# xmos.net
KiCad netlist of a schematic drawn in Altium Designer
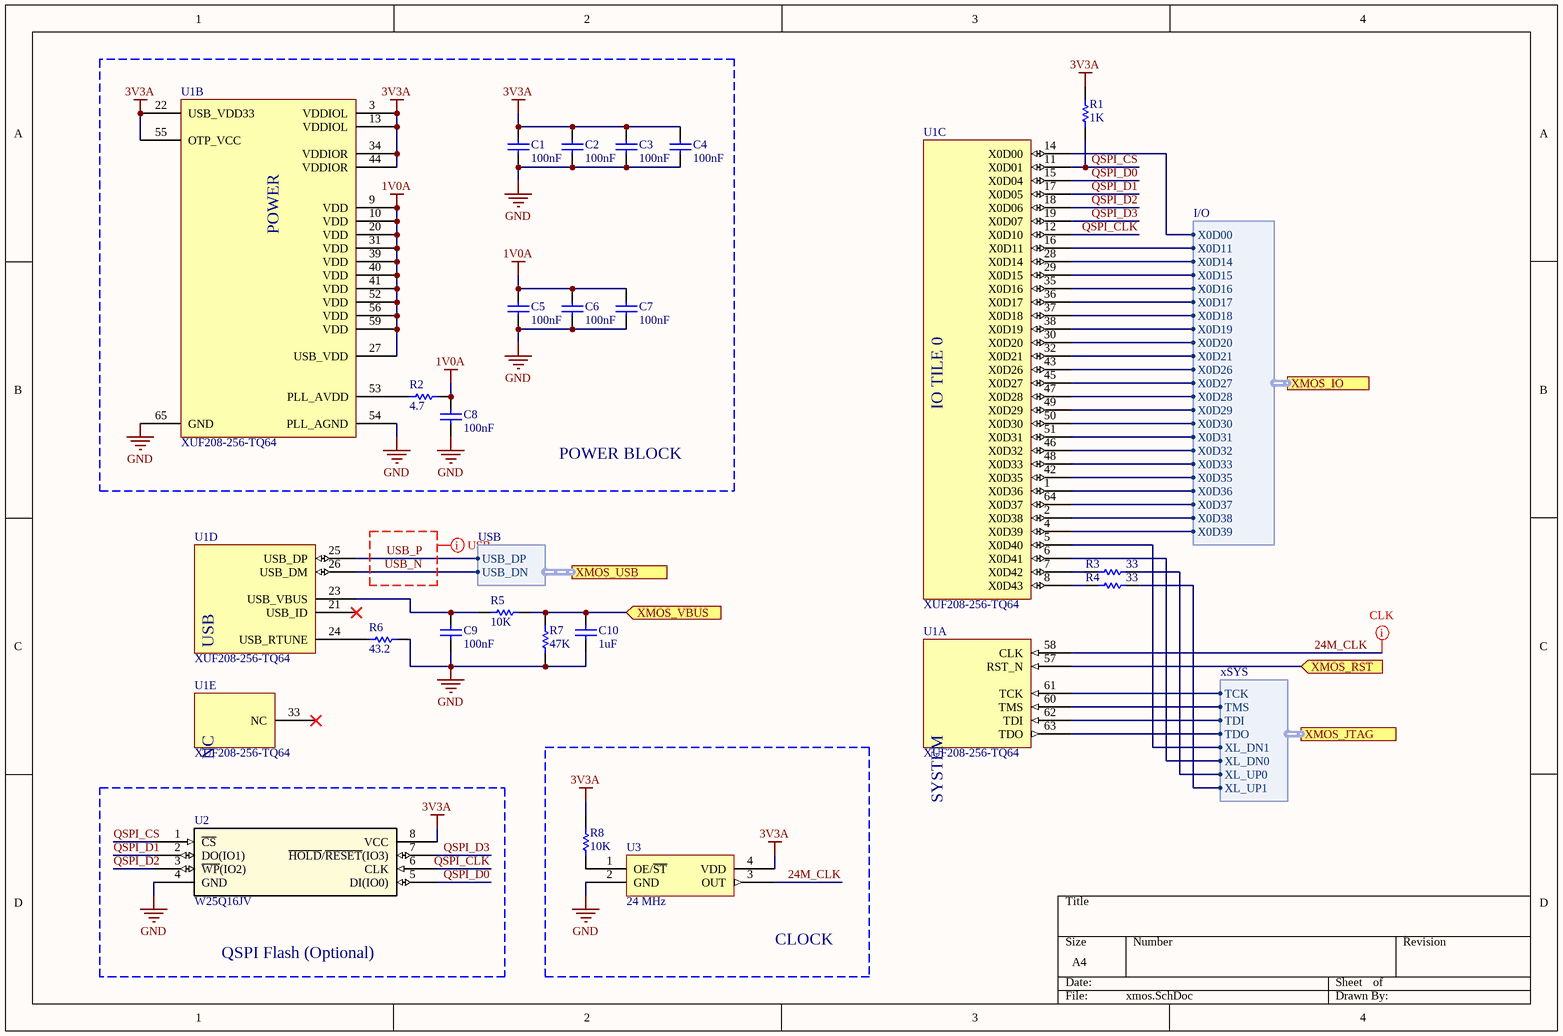
[diagram p0: xmos.SchDoc]

(export (version "E")
  (design (tool "Eeschema 10.0.6"))
  (components
    (comp (ref "C1")
      (value "100nF")
      (footprint "CAP_0603")
      (description "Multilayer Ceramic Capacitors")
      (fields (field (name "TOLERANCE") "10%") (field (name "Comment") "MLCC"))
      (libsource (lib "Capacitors") (part "MLCC"))
    )
    (comp (ref "C2")
      (value "100nF")
      (footprint "CAP_0603")
      (description "Multilayer Ceramic Capacitors")
      (fields (field (name "TOLERANCE") "10%") (field (name "Comment") "MLCC"))
      (libsource (lib "Capacitors") (part "MLCC"))
    )
    (comp (ref "C3")
      (value "100nF")
      (footprint "CAP_0603")
      (description "Multilayer Ceramic Capacitors")
      (fields (field (name "TOLERANCE") "10%") (field (name "Comment") "MLCC"))
      (libsource (lib "Capacitors") (part "MLCC"))
    )
    (comp (ref "C4")
      (value "100nF")
      (footprint "CAP_0603")
      (description "Multilayer Ceramic Capacitors")
      (fields (field (name "TOLERANCE") "10%") (field (name "Comment") "MLCC"))
      (libsource (lib "Capacitors") (part "MLCC"))
    )
    (comp (ref "C5")
      (value "100nF")
      (footprint "CAP_0603")
      (description "Multilayer Ceramic Capacitors")
      (fields (field (name "TOLERANCE") "10%") (field (name "Comment") "MLCC"))
      (libsource (lib "Capacitors") (part "MLCC"))
    )
    (comp (ref "C6")
      (value "100nF")
      (footprint "CAP_0603")
      (description "Multilayer Ceramic Capacitors")
      (fields (field (name "TOLERANCE") "10%") (field (name "Comment") "MLCC"))
      (libsource (lib "Capacitors") (part "MLCC"))
    )
    (comp (ref "C7")
      (value "100nF")
      (footprint "CAP_0603")
      (description "Multilayer Ceramic Capacitors")
      (fields (field (name "TOLERANCE") "10%") (field (name "Comment") "MLCC"))
      (libsource (lib "Capacitors") (part "MLCC"))
    )
    (comp (ref "C8")
      (value "100nF")
      (footprint "CAP_0603")
      (description "Multilayer Ceramic Capacitors")
      (fields (field (name "TOLERANCE") "10%") (field (name "Comment") "MLCC"))
      (libsource (lib "Capacitors") (part "MLCC"))
    )
    (comp (ref "C9")
      (value "100nF")
      (footprint "CAP_0603")
      (description "Multilayer Ceramic Capacitors")
      (fields (field (name "TOLERANCE") "10%") (field (name "Comment") "MLCC"))
      (libsource (lib "Capacitors") (part "MLCC"))
    )
    (comp (ref "C10")
      (value "1uF")
      (footprint "CAP_0603")
      (description "Multilayer Ceramic Capacitors")
      (fields (field (name "TOLERANCE") "10%") (field (name "Comment") "MLCC"))
      (libsource (lib "Capacitors") (part "MLCC"))
    )
    (comp (ref "R1")
      (value "1K")
      (footprint "RC0603N")
      (description "Chip Resistors")
      (fields (field (name "Comment") "RES"))
      (libsource (lib "Resistors") (part "RES"))
    )
    (comp (ref "R2")
      (value "4.7")
      (footprint "RC0603N")
      (description "Chip Resistors")
      (fields (field (name "Comment") "RES"))
      (libsource (lib "Resistors") (part "RES"))
    )
    (comp (ref "R3")
      (value "33")
      (footprint "RC0603N")
      (description "Chip Resistors")
      (fields (field (name "Comment") "RES"))
      (libsource (lib "Resistors") (part "RES"))
    )
    (comp (ref "R4")
      (value "33")
      (footprint "RC0603N")
      (description "Chip Resistors")
      (fields (field (name "Comment") "RES"))
      (libsource (lib "Resistors") (part "RES"))
    )
    (comp (ref "R5")
      (value "10K")
      (footprint "RC0603N")
      (description "Chip Resistors")
      (fields (field (name "Comment") "RES"))
      (libsource (lib "Resistors") (part "RES"))
    )
    (comp (ref "R6")
      (value "43.2")
      (footprint "RC0603N")
      (description "Chip Resistors")
      (fields (field (name "Comment") "RES"))
      (libsource (lib "Resistors") (part "RES"))
    )
    (comp (ref "R7")
      (value "47K")
      (footprint "RC0603N")
      (description "Chip Resistors")
      (fields (field (name "Comment") "RES"))
      (libsource (lib "Resistors") (part "RES"))
    )
    (comp (ref "R8")
      (value "10K")
      (footprint "RC0603N")
      (description "Chip Resistors")
      (fields (field (name "Comment") "RES"))
      (libsource (lib "Resistors") (part "RES"))
    )
    (comp (ref "U1")
      (value "XUF208-256-TQ64")
      (footprint "TQ64")
      (description "xCORE Multicore Microcontroller, xCORE-200, USB, Single Tile, 8 Cores, 500MHz, 64TQFP")
      (fields (field (name "MANUFACTURER") "XMOS"))
      (libsource (lib "XMOS") (part "XUF208-256-TQ64"))
    )
    (comp (ref "U2")
      (value "W25Q16JV")
      (footprint "SOIC-8_150MIL")
      (description "3V 16M-BIT SERIAL FLASH MEMORY WITH DUAL/QUAD SPI")
      (fields
        (field (name "MANUFACTURER_PART_NUMBER") "W25Q16JVXXXX")
        (field (name "COPYRIGHT") "Copyright (C) 2018 Accelerated Designs. All rights reserved")
      )
      (libsource (lib "WINBOND") (part "W25Q16JV"))
    )
    (comp (ref "U3")
      (value "XO")
      (footprint "QFN_3225_4P")
      (description "SiTime Ultra Performance Oscillator")
      (fields (field (name "MANUFACTURER") "SiTime") (field (name "FREQUENCY") "24 MHz"))
      (libsource (lib "Crystals") (part "XO"))
    )
  )
  (nets
    (net (code "4") (name "/24M_CLK") (class "Default")
      (node (ref "U1") (pin "58") (pinfunction "CLK_58") (pintype "input"))
      (node (ref "U3") (pin "3") (pinfunction "OUT_3") (pintype "output"))
    )
    (net (code "5") (name "/QSPI_CLK") (class "Default")
      (node (ref "U1") (pin "12") (pinfunction "X0D10_12") (pintype "bidirectional"))
      (node (ref "U2") (pin "6") (pinfunction "CLK_6") (pintype "input"))
    )
    (net (code "6") (name "/QSPI_CS") (class "Default")
      (node (ref "R1") (pin "1") (pinfunction "1_1") (pintype "passive"))
      (node (ref "U1") (pin "11") (pinfunction "X0D01_11") (pintype "bidirectional"))
      (node (ref "U2") (pin "1") (pinfunction "~{CS}_1") (pintype "input"))
    )
    (net (code "7") (name "/QSPI_D0") (class "Default")
      (node (ref "U1") (pin "15") (pinfunction "X0D04_15") (pintype "bidirectional"))
      (node (ref "U2") (pin "5") (pinfunction "DI(IO0)_5") (pintype "bidirectional"))
    )
    (net (code "8") (name "/QSPI_D1") (class "Default")
      (node (ref "U1") (pin "17") (pinfunction "X0D05_17") (pintype "bidirectional"))
      (node (ref "U2") (pin "2") (pinfunction "DO(IO1)_2") (pintype "bidirectional"))
    )
    (net (code "9") (name "/QSPI_D2") (class "Default")
      (node (ref "U1") (pin "18") (pinfunction "X0D06_18") (pintype "bidirectional"))
      (node (ref "U2") (pin "3") (pinfunction "~{WP}(IO2)_3") (pintype "bidirectional"))
    )
    (net (code "10") (name "/QSPI_D3") (class "Default")
      (node (ref "U1") (pin "19") (pinfunction "X0D07_19") (pintype "bidirectional"))
      (node (ref "U2") (pin "7") (pinfunction "~{HOLD}/~{RESET}(IO3)_7") (pintype "bidirectional"))
    )
    (net (code "11") (name "/TCK") (class "Default")
      (node (ref "U1") (pin "61") (pinfunction "TCK_61") (pintype "input"))
    )
    (net (code "12") (name "/TDI") (class "Default")
      (node (ref "U1") (pin "62") (pinfunction "TDI_62") (pintype "input"))
    )
    (net (code "13") (name "/TDO") (class "Default")
      (node (ref "U1") (pin "63") (pinfunction "TDO_63") (pintype "output"))
    )
    (net (code "14") (name "/TMS") (class "Default")
      (node (ref "U1") (pin "60") (pinfunction "TMS_60") (pintype "input"))
    )
    (net (code "15") (name "/USB_N") (class "Default")
      (node (ref "U1") (pin "26") (pinfunction "USB_DM_26") (pintype "bidirectional"))
    )
    (net (code "16") (name "/USB_P") (class "Default")
      (node (ref "U1") (pin "25") (pinfunction "USB_DP_25") (pintype "bidirectional"))
    )
    (net (code "17") (name "/X0D00") (class "Default")
      (node (ref "U1") (pin "14") (pinfunction "X0D00_14") (pintype "bidirectional"))
    )
    (net (code "18") (name "/X0D11") (class "Default")
      (node (ref "U1") (pin "16") (pinfunction "X0D11_16") (pintype "bidirectional"))
    )
    (net (code "19") (name "/X0D14") (class "Default")
      (node (ref "U1") (pin "28") (pinfunction "X0D14_28") (pintype "bidirectional"))
    )
    (net (code "20") (name "/X0D15") (class "Default")
      (node (ref "U1") (pin "29") (pinfunction "X0D15_29") (pintype "bidirectional"))
    )
    (net (code "21") (name "/X0D16") (class "Default")
      (node (ref "U1") (pin "35") (pinfunction "X0D16_35") (pintype "bidirectional"))
    )
    (net (code "22") (name "/X0D17") (class "Default")
      (node (ref "U1") (pin "36") (pinfunction "X0D17_36") (pintype "bidirectional"))
    )
    (net (code "23") (name "/X0D18") (class "Default")
      (node (ref "U1") (pin "37") (pinfunction "X0D18_37") (pintype "bidirectional"))
    )
    (net (code "24") (name "/X0D19") (class "Default")
      (node (ref "U1") (pin "38") (pinfunction "X0D19_38") (pintype "bidirectional"))
    )
    (net (code "25") (name "/X0D20") (class "Default")
      (node (ref "U1") (pin "30") (pinfunction "X0D20_30") (pintype "bidirectional"))
    )
    (net (code "26") (name "/X0D21") (class "Default")
      (node (ref "U1") (pin "32") (pinfunction "X0D21_32") (pintype "bidirectional"))
    )
    (net (code "27") (name "/X0D26") (class "Default")
      (node (ref "U1") (pin "43") (pinfunction "X0D26_43") (pintype "bidirectional"))
    )
    (net (code "28") (name "/X0D27") (class "Default")
      (node (ref "U1") (pin "45") (pinfunction "X0D27_45") (pintype "bidirectional"))
    )
    (net (code "29") (name "/X0D28") (class "Default")
      (node (ref "U1") (pin "47") (pinfunction "X0D28_47") (pintype "bidirectional"))
    )
    (net (code "30") (name "/X0D29") (class "Default")
      (node (ref "U1") (pin "49") (pinfunction "X0D29_49") (pintype "bidirectional"))
    )
    (net (code "31") (name "/X0D30") (class "Default")
      (node (ref "U1") (pin "50") (pinfunction "X0D30_50") (pintype "bidirectional"))
    )
    (net (code "32") (name "/X0D31") (class "Default")
      (node (ref "U1") (pin "51") (pinfunction "X0D31_51") (pintype "bidirectional"))
    )
    (net (code "33") (name "/X0D32") (class "Default")
      (node (ref "U1") (pin "46") (pinfunction "X0D32_46") (pintype "bidirectional"))
    )
    (net (code "34") (name "/X0D33") (class "Default")
      (node (ref "U1") (pin "48") (pinfunction "X0D33_48") (pintype "bidirectional"))
    )
    (net (code "35") (name "/X0D35") (class "Default")
      (node (ref "U1") (pin "42") (pinfunction "X0D35_42") (pintype "bidirectional"))
    )
    (net (code "36") (name "/X0D36") (class "Default")
      (node (ref "U1") (pin "1") (pinfunction "X0D36_1") (pintype "bidirectional"))
    )
    (net (code "37") (name "/X0D37") (class "Default")
      (node (ref "U1") (pin "64") (pinfunction "X0D37_64") (pintype "bidirectional"))
    )
    (net (code "38") (name "/X0D38") (class "Default")
      (node (ref "U1") (pin "2") (pinfunction "X0D38_2") (pintype "bidirectional"))
    )
    (net (code "39") (name "/X0D39") (class "Default")
      (node (ref "U1") (pin "4") (pinfunction "X0D39_4") (pintype "bidirectional"))
    )
    (net (code "40") (name "/XL_DN0") (class "Default")
      (node (ref "U1") (pin "6") (pinfunction "X0D41_6") (pintype "bidirectional"))
    )
    (net (code "41") (name "/XL_DN1") (class "Default")
      (node (ref "U1") (pin "5") (pinfunction "X0D40_5") (pintype "bidirectional"))
    )
    (net (code "42") (name "/XL_UP0") (class "Default")
      (node (ref "R3") (pin "2") (pinfunction "2_2") (pintype "passive"))
    )
    (net (code "43") (name "/XL_UP1") (class "Default")
      (node (ref "R4") (pin "2") (pinfunction "2_2") (pintype "passive"))
    )
    (net (code "44") (name "/XMOS_RST") (class "Default")
      (node (ref "U1") (pin "57") (pinfunction "RST_N_57") (pintype "input"))
    )
    (net (code "45") (name "/XMOS_VBUS") (class "Default")
      (node (ref "C10") (pin "1") (pinfunction "1_1") (pintype "passive"))
      (node (ref "R5") (pin "2") (pinfunction "2_2") (pintype "passive"))
      (node (ref "R7") (pin "2") (pinfunction "2_2") (pintype "passive"))
    )
    (net (code "49") (name "1V0A") (class "Default")
      (node (ref "C5") (pin "2") (pinfunction "2_2") (pintype "passive"))
      (node (ref "C6") (pin "2") (pinfunction "2_2") (pintype "passive"))
      (node (ref "C7") (pin "2") (pinfunction "2_2") (pintype "passive"))
      (node (ref "C8") (pin "2") (pinfunction "2_2") (pintype "passive"))
      (node (ref "R2") (pin "2") (pinfunction "2_2") (pintype "passive"))
      (node (ref "U1") (pin "10") (pinfunction "VDD_10") (pintype "power_in"))
      (node (ref "U1") (pin "20") (pinfunction "VDD_20") (pintype "power_in"))
      (node (ref "U1") (pin "27") (pinfunction "USB_VDD_27") (pintype "power_in"))
      (node (ref "U1") (pin "31") (pinfunction "VDD_31") (pintype "power_in"))
      (node (ref "U1") (pin "39") (pinfunction "VDD_39") (pintype "power_in"))
      (node (ref "U1") (pin "40") (pinfunction "VDD_40") (pintype "power_in"))
      (node (ref "U1") (pin "41") (pinfunction "VDD_41") (pintype "power_in"))
      (node (ref "U1") (pin "52") (pinfunction "VDD_52") (pintype "power_in"))
      (node (ref "U1") (pin "56") (pinfunction "VDD_56") (pintype "power_in"))
      (node (ref "U1") (pin "59") (pinfunction "VDD_59") (pintype "power_in"))
      (node (ref "U1") (pin "9") (pinfunction "VDD_9") (pintype "power_in"))
    )
    (net (code "50") (name "3V3A") (class "Default")
      (node (ref "C1") (pin "2") (pinfunction "2_2") (pintype "passive"))
      (node (ref "C2") (pin "2") (pinfunction "2_2") (pintype "passive"))
      (node (ref "C3") (pin "2") (pinfunction "2_2") (pintype "passive"))
      (node (ref "C4") (pin "2") (pinfunction "2_2") (pintype "passive"))
      (node (ref "R1") (pin "2") (pinfunction "2_2") (pintype "passive"))
      (node (ref "R8") (pin "2") (pinfunction "2_2") (pintype "passive"))
      (node (ref "U1") (pin "13") (pinfunction "VDDIOL_13") (pintype "power_in"))
      (node (ref "U1") (pin "22") (pinfunction "USB_VDD33_22") (pintype "power_in"))
      (node (ref "U1") (pin "3") (pinfunction "VDDIOL_3") (pintype "power_in"))
      (node (ref "U1") (pin "34") (pinfunction "VDDIOR_34") (pintype "power_in"))
      (node (ref "U1") (pin "44") (pinfunction "VDDIOR_44") (pintype "power_in"))
      (node (ref "U1") (pin "55") (pinfunction "OTP_VCC_55") (pintype "power_in"))
      (node (ref "U2") (pin "8") (pinfunction "VCC_8") (pintype "power_in"))
      (node (ref "U3") (pin "4") (pinfunction "VDD_4") (pintype "power_in"))
    )
    (net (code "51") (name "GND") (class "Default")
      (node (ref "C1") (pin "1") (pinfunction "1_1") (pintype "passive"))
      (node (ref "C10") (pin "2") (pinfunction "2_2") (pintype "passive"))
      (node (ref "C2") (pin "1") (pinfunction "1_1") (pintype "passive"))
      (node (ref "C3") (pin "1") (pinfunction "1_1") (pintype "passive"))
      (node (ref "C4") (pin "1") (pinfunction "1_1") (pintype "passive"))
      (node (ref "C5") (pin "1") (pinfunction "1_1") (pintype "passive"))
      (node (ref "C6") (pin "1") (pinfunction "1_1") (pintype "passive"))
      (node (ref "C7") (pin "1") (pinfunction "1_1") (pintype "passive"))
      (node (ref "C8") (pin "1") (pinfunction "1_1") (pintype "passive"))
      (node (ref "C9") (pin "1") (pinfunction "1_1") (pintype "passive"))
      (node (ref "R6") (pin "2") (pinfunction "2_2") (pintype "passive"))
      (node (ref "R7") (pin "1") (pinfunction "1_1") (pintype "passive"))
      (node (ref "U1") (pin "54") (pinfunction "PLL_AGND_54") (pintype "power_in"))
      (node (ref "U1") (pin "65") (pinfunction "GND_65") (pintype "power_in"))
      (node (ref "U2") (pin "4") (pinfunction "GND_4") (pintype "passive"))
      (node (ref "U3") (pin "2") (pinfunction "GND_2") (pintype "passive"))
    )
    (net (code "52") (name "Net-(U1B-PLL_AVDD)") (class "Default")
      (node (ref "R2") (pin "1") (pinfunction "1_1") (pintype "passive"))
      (node (ref "U1") (pin "53") (pinfunction "PLL_AVDD_53") (pintype "power_in"))
    )
    (net (code "53") (name "Net-(U1C-X0D42)") (class "Default")
      (node (ref "R3") (pin "1") (pinfunction "1_1") (pintype "passive"))
      (node (ref "U1") (pin "7") (pinfunction "X0D42_7") (pintype "bidirectional"))
    )
    (net (code "54") (name "Net-(U1C-X0D43)") (class "Default")
      (node (ref "R4") (pin "1") (pinfunction "1_1") (pintype "passive"))
      (node (ref "U1") (pin "8") (pinfunction "X0D43_8") (pintype "bidirectional"))
    )
    (net (code "55") (name "Net-(U1D-USB_RTUNE)") (class "Default")
      (node (ref "R6") (pin "1") (pinfunction "1_1") (pintype "passive"))
      (node (ref "U1") (pin "24") (pinfunction "USB_RTUNE_24") (pintype "passive"))
    )
    (net (code "56") (name "Net-(U1D-USB_VBUS)") (class "Default")
      (node (ref "C9") (pin "2") (pinfunction "2_2") (pintype "passive"))
      (node (ref "R5") (pin "1") (pinfunction "1_1") (pintype "passive"))
      (node (ref "U1") (pin "23") (pinfunction "USB_VBUS_23") (pintype "passive"))
    )
    (net (code "57") (name "Net-(U3-OE{slash}~{ST})") (class "Default")
      (node (ref "R8") (pin "1") (pinfunction "1_1") (pintype "passive"))
      (node (ref "U3") (pin "1") (pinfunction "OE/~{ST}_1") (pintype "passive"))
    )
    (net (code "58") (name "unconnected-(U1D-USB_ID-Pad21)") (class "Default")
      (node (ref "U1") (pin "21") (pinfunction "USB_ID_21") (pintype "passive+no_connect"))
    )
    (net (code "59") (name "unconnected-(U1E-NC-Pad33)") (class "Default")
      (node (ref "U1") (pin "33") (pinfunction "NC_33") (pintype "passive+no_connect"))
    )
  )
)
